# ESP32S2-new_sensor_device_v1_0-_ENV_MOT_.net
KiCad netlist of a schematic drawn in EasyEDA
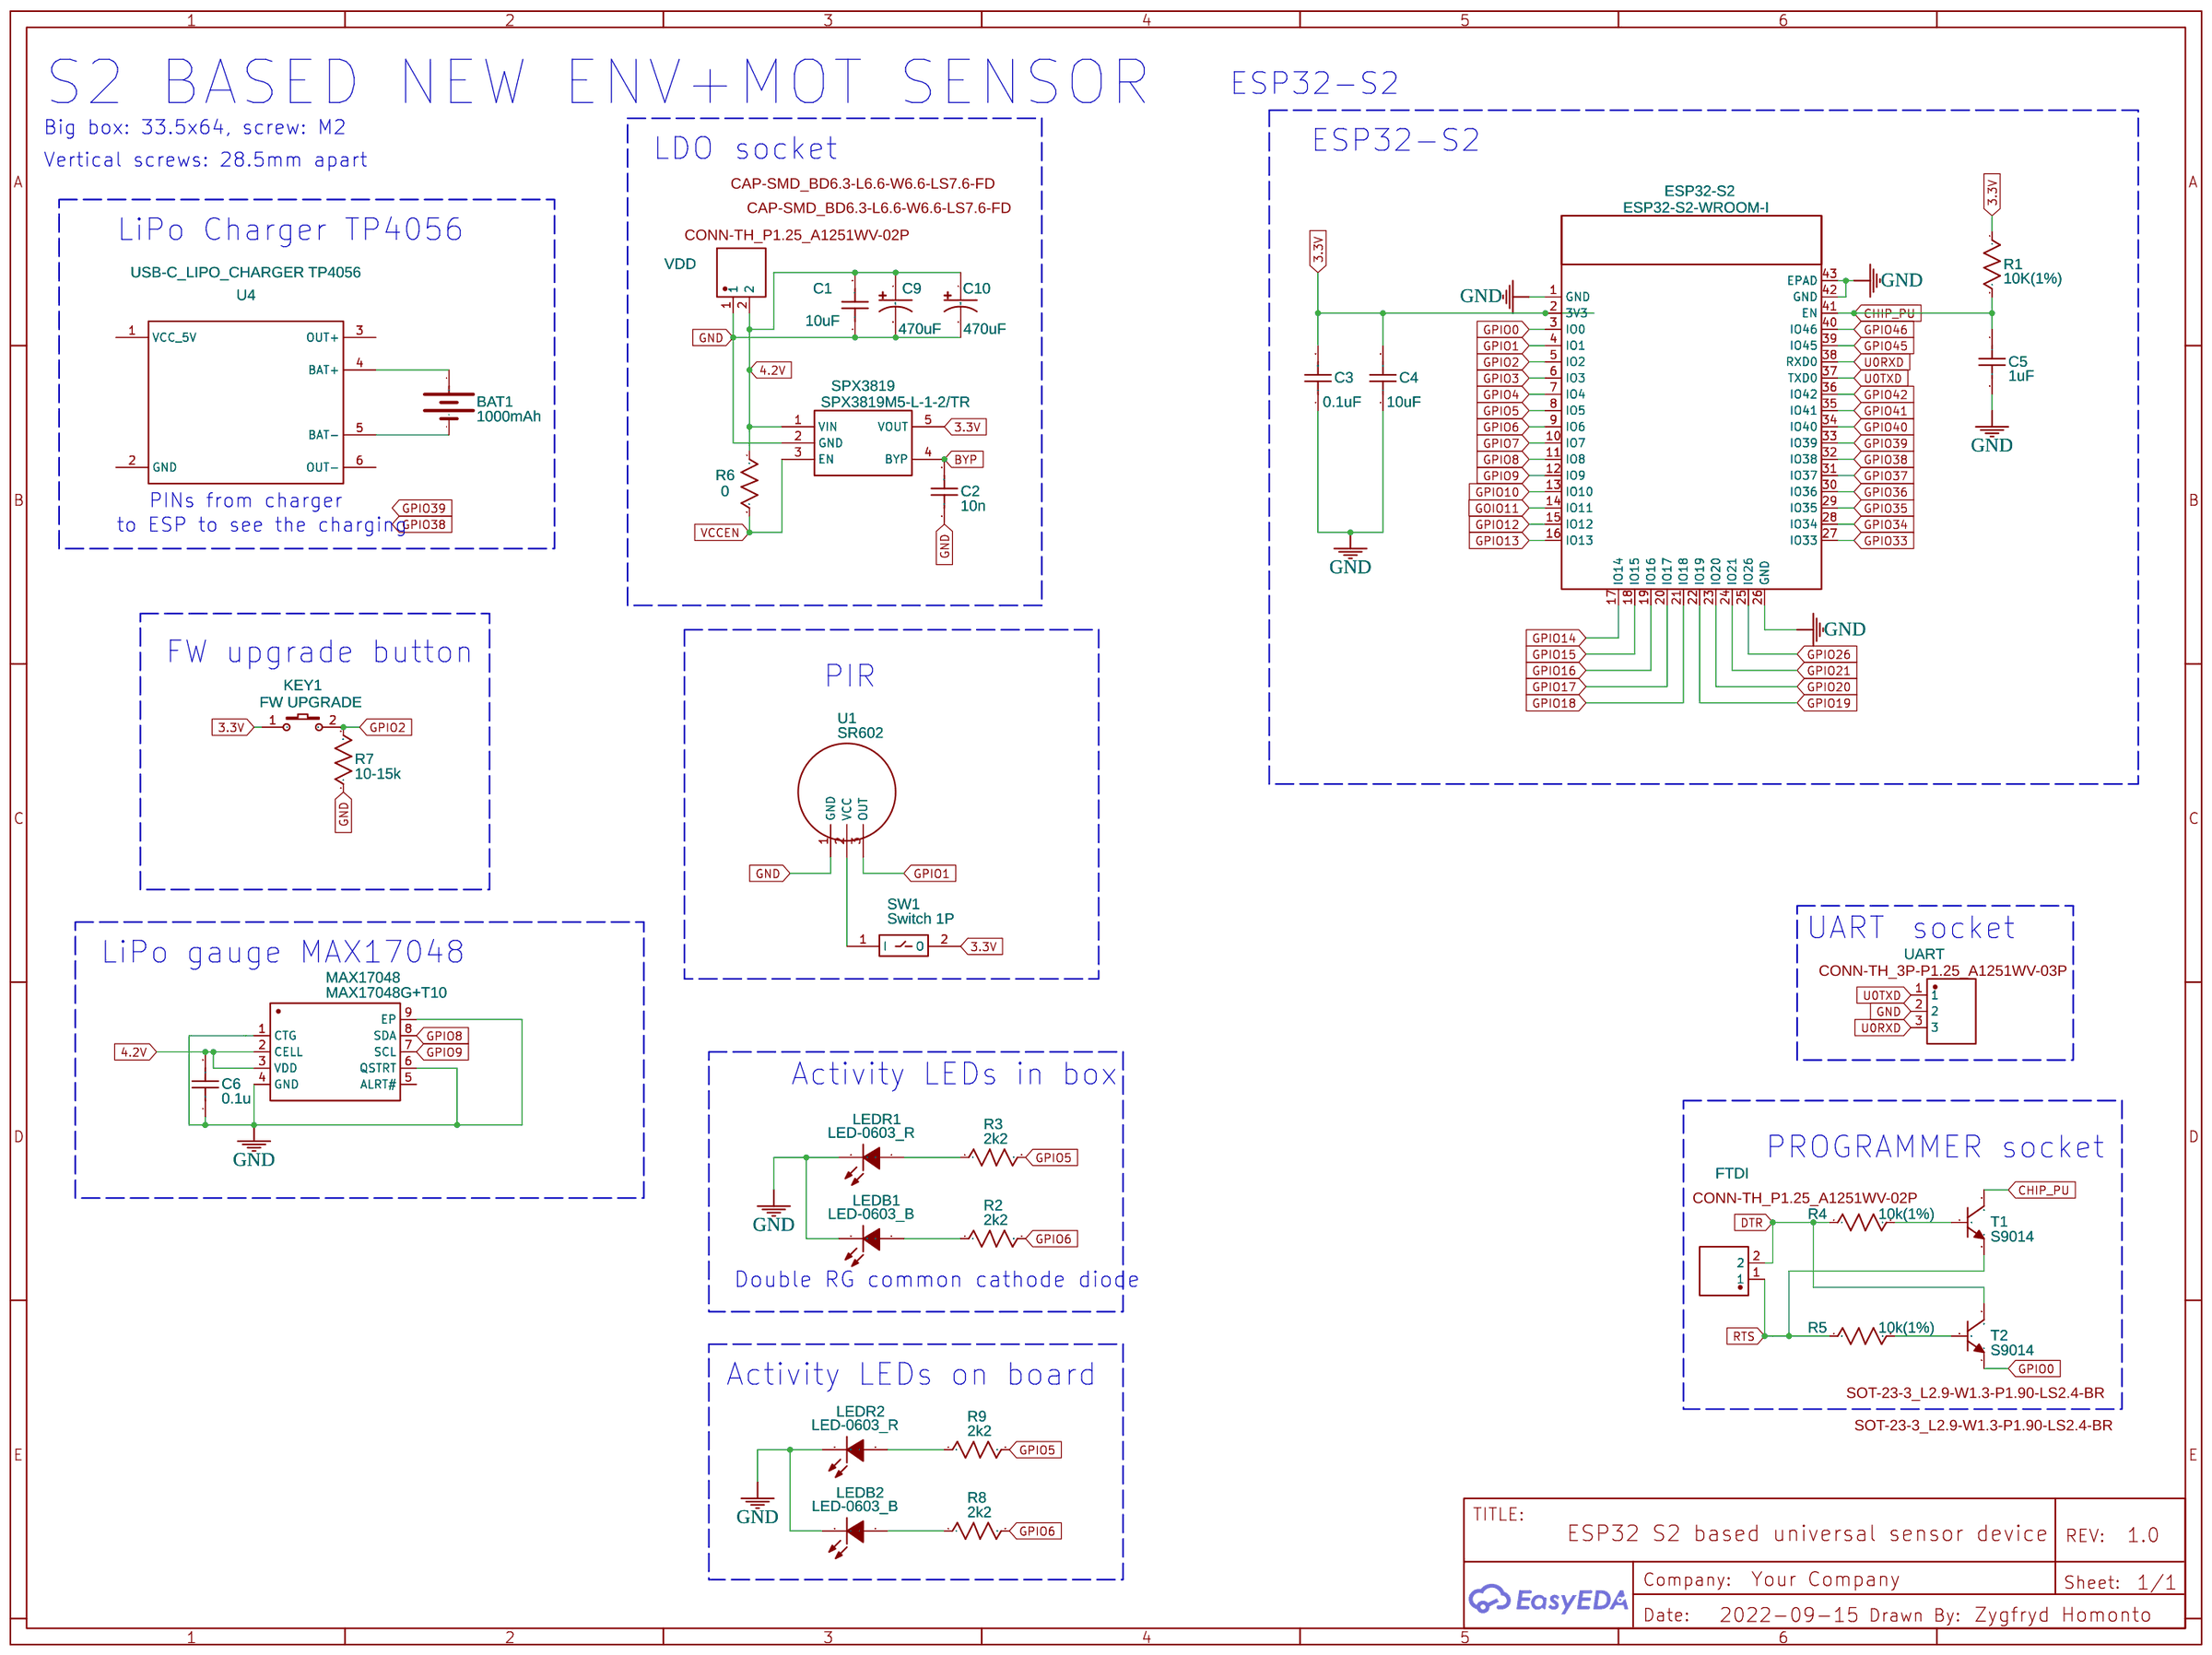
[diagram p0: schematic sheet]

(export (version "E")
  (design (tool "Eeschema 10.0.6"))
  (components
    (comp (ref "BAT1") (value "1000mAh") (libsource (lib "") (part "BATTERY")))
    (comp (ref "C1") (value "10uF") (libsource (lib "") (part "C_0201_US")))
    (comp (ref "C2") (value "10n") (libsource (lib "") (part "C_0603_US")))
    (comp (ref "C3") (value "0.1uF") (libsource (lib "") (part "C_0201_US")))
    (comp (ref "C4") (value "10uF") (libsource (lib "") (part "C_0201_US")))
    (comp (ref "C5") (value "1uF") (libsource (lib "") (part "C_0201_US_1")))
    (comp (ref "C6") (value "0.1u") (libsource (lib "") (part "C_0603_US")))
    (comp (ref "C9")
      (value "470uF")
      (fields
        (field (name "BOM_Manufacturer Part") "BXJ-16V220-6.3*7.7")
        (field (name "BOM_Supplier Part") "C165635")
      )
      (libsource (lib "") (part "BXJ-16V220-6.3*7.7_1"))
    )
    (comp (ref "C10")
      (value "470uF")
      (fields
        (field (name "BOM_Manufacturer Part") "BXJ-16V220-6.3*7.7")
        (field (name "BOM_Supplier Part") "C165635")
      )
      (libsource (lib "") (part "BXJ-16V220-6.3*7.7"))
    )
    (comp (ref "ESP32-S2")
      (value "ESP32-S2-WROOM-I")
      (fields (field (name "BOM_Manufacturer Part") "ESP32-S2-WROOM"))
      (libsource (lib "") (part "ESP32-S2-WROOM"))
    )
    (comp (ref "FTDI")
      (value "A1251WR-2P")
      (fields (field (name "BOM_Supplier Part") "C225097"))
      (libsource (lib "") (part "A1251WR-2P"))
    )
    (comp (ref "KEY1")
      (value "FW UPGRADE")
      (fields
        (field (name "BOM_Manufacturer Part") "K2-1107ST-A4SW-06")
        (field (name "BOM_Supplier Part") "C118141")
      )
      (libsource (lib "") (part "K2-3.6×6.1_SMD"))
    )
    (comp (ref "LEDB1")
      (value "LED-0603_B")
      (fields
        (field (name "BOM_Manufacturer Part") "19-217/BHC-ZL1M2RY/3T")
        (field (name "BOM_Supplier Part") "C72041")
      )
      (libsource (lib "") (part "LED-0603_B"))
    )
    (comp (ref "LEDB2")
      (value "LED-0603_B")
      (fields
        (field (name "BOM_Manufacturer Part") "19-217/BHC-ZL1M2RY/3T")
        (field (name "BOM_Supplier Part") "C72041")
      )
      (libsource (lib "") (part "LED-0603_B"))
    )
    (comp (ref "LEDR1")
      (value "LED-0603_R")
      (fields
        (field (name "BOM_Manufacturer Part") "19-217/R6C-AL1M2VY/3T")
        (field (name "BOM_Supplier Part") "C72044")
      )
      (libsource (lib "") (part "LED-0603_R"))
    )
    (comp (ref "LEDR2")
      (value "LED-0603_R")
      (fields
        (field (name "BOM_Manufacturer Part") "19-217/R6C-AL1M2VY/3T")
        (field (name "BOM_Supplier Part") "C72044")
      )
      (libsource (lib "") (part "LED-0603_R"))
    )
    (comp (ref "MAX17048")
      (value "MAX17048G+T10")
      (fields (field (name "BOM_Supplier Part") "C2682616"))
      (libsource (lib "") (part "MAX17048G+T10"))
    )
    (comp (ref "R1") (value "10K(1%)") (libsource (lib "") (part "R_0201_US_2")))
    (comp (ref "R2") (value "2k2") (libsource (lib "") (part "R_0201_US")))
    (comp (ref "R3") (value "2k2") (libsource (lib "") (part "R_0201_US")))
    (comp (ref "R4") (value "10k(1%)") (libsource (lib "") (part "R_0201_US")))
    (comp (ref "R5") (value "10k(1%)") (libsource (lib "") (part "R_0201_US")))
    (comp (ref "R6") (value "0") (libsource (lib "") (part "R_0201_US_2")))
    (comp (ref "R7") (value "10-15k") (libsource (lib "") (part "R_0201_US_1")))
    (comp (ref "R8") (value "2k2") (libsource (lib "") (part "R_0201_US")))
    (comp (ref "R9") (value "2k2") (libsource (lib "") (part "R_0201_US")))
    (comp (ref "SPX3819")
      (value "SPX3819M5-L-1-2/TR")
      (fields (field (name "BOM_Supplier Part") "C54988"))
      (libsource (lib "") (part "SPX3819M5-L-1-2/TR"))
    )
    (comp (ref "SW1") (value "Switch 1P") (libsource (lib "") (part "Switch 1P")))
    (comp (ref "T1")
      (value "S9014")
      (fields
        (field (name "BOM_Manufacturer Part") "S9014LT1 (S9014 J6)")
        (field (name "BOM_Supplier Part") "C2148")
      )
      (libsource (lib "") (part "S9014LT1 (S9014 J6)"))
    )
    (comp (ref "T2")
      (value "S9014")
      (fields
        (field (name "BOM_Manufacturer Part") "S9014LT1 (S9014 J6)")
        (field (name "BOM_Supplier Part") "C2148")
      )
      (libsource (lib "") (part "S9014LT1 (S9014 J6)_1"))
    )
    (comp (ref "U1") (value "SR602") (libsource (lib "") (part "SR602")))
    (comp (ref "U4") (value "USB-C_LIPO_CHARGER TP4056") (libsource (lib "") (part "USB_LIPO_CHARGER")))
    (comp (ref "UART")
      (value "A1251WR-3P")
      (fields (field (name "BOM_Supplier Part") "C225098"))
      (libsource (lib "") (part "A1251WR-3P"))
    )
    (comp (ref "VDD")
      (value "A1251WR-2P")
      (fields (field (name "BOM_Supplier Part") "C225097"))
      (libsource (lib "") (part "A1251WR-2P_1"))
    )
  )
  (nets
    (net (code "1") (name "3.3V") (class "Default")
      (node (ref "C3") (pin "2") (pinfunction "2_2") (pintype "unspecified"))
      (node (ref "C4") (pin "2") (pinfunction "2_2") (pintype "unspecified"))
      (node (ref "ESP32-S2") (pin "2") (pinfunction "3V3_2") (pintype "unspecified"))
      (node (ref "KEY1") (pin "1") (pinfunction "1_1") (pintype "unspecified"))
      (node (ref "R1") (pin "1") (pinfunction "1_1") (pintype "unspecified"))
      (node (ref "SPX3819") (pin "5") (pinfunction "VOUT_5") (pintype "unspecified"))
      (node (ref "SW1") (pin "2") (pinfunction "O_2") (pintype "unspecified"))
    )
    (net (code "2") (name "4.2V") (class "Default")
      (node (ref "C1") (pin "2") (pinfunction "2_2") (pintype "unspecified"))
      (node (ref "C10") (pin "1") (pinfunction "1_1") (pintype "unspecified"))
      (node (ref "C6") (pin "2") (pinfunction "2_2") (pintype "unspecified"))
      (node (ref "C9") (pin "1") (pinfunction "1_1") (pintype "unspecified"))
      (node (ref "MAX17048") (pin "2") (pinfunction "CELL_2") (pintype "unspecified"))
      (node (ref "MAX17048") (pin "3") (pinfunction "VDD_3") (pintype "unspecified"))
      (node (ref "R6") (pin "1") (pinfunction "1_1") (pintype "unspecified"))
      (node (ref "SPX3819") (pin "1") (pinfunction "VIN_1") (pintype "unspecified"))
      (node (ref "VDD") (pin "2") (pinfunction "2_2") (pintype "unspecified"))
    )
    (net (code "3") (name "BYP") (class "Default")
      (node (ref "C2") (pin "2") (pinfunction "2_2") (pintype "unspecified"))
      (node (ref "SPX3819") (pin "4") (pinfunction "BYP_4") (pintype "unspecified"))
    )
    (net (code "4") (name "CHIP_PU") (class "Default")
      (node (ref "C5") (pin "1") (pinfunction "1_1") (pintype "unspecified"))
      (node (ref "ESP32-S2") (pin "41") (pinfunction "EN_41") (pintype "unspecified"))
      (node (ref "R1") (pin "2") (pinfunction "2_2") (pintype "unspecified"))
      (node (ref "T1") (pin "3") (pinfunction "C_3") (pintype "unspecified"))
    )
    (net (code "5") (name "DTR") (class "Default")
      (node (ref "FTDI") (pin "2") (pinfunction "2_2") (pintype "unspecified"))
      (node (ref "R4") (pin "1") (pinfunction "1_1") (pintype "unspecified"))
      (node (ref "T2") (pin "3") (pinfunction "C_3") (pintype "unspecified"))
    )
    (net (code "6") (name "GND") (class "Default")
      (node (ref "C1") (pin "1") (pinfunction "1_1") (pintype "unspecified"))
      (node (ref "C10") (pin "2") (pinfunction "2_2") (pintype "unspecified"))
      (node (ref "C2") (pin "1") (pinfunction "1_1") (pintype "unspecified"))
      (node (ref "C3") (pin "1") (pinfunction "1_1") (pintype "unspecified"))
      (node (ref "C4") (pin "1") (pinfunction "1_1") (pintype "unspecified"))
      (node (ref "C5") (pin "2") (pinfunction "2_2") (pintype "unspecified"))
      (node (ref "C6") (pin "1") (pinfunction "1_1") (pintype "unspecified"))
      (node (ref "C9") (pin "2") (pinfunction "2_2") (pintype "unspecified"))
      (node (ref "ESP32-S2") (pin "1") (pinfunction "GND_1") (pintype "unspecified"))
      (node (ref "ESP32-S2") (pin "26") (pinfunction "GND_26") (pintype "unspecified"))
      (node (ref "ESP32-S2") (pin "42") (pinfunction "GND_42") (pintype "unspecified"))
      (node (ref "ESP32-S2") (pin "43") (pinfunction "EPAD_43") (pintype "unspecified"))
      (node (ref "LEDB1") (pin "2") (pinfunction "2_2") (pintype "unspecified"))
      (node (ref "LEDB2") (pin "2") (pinfunction "2_2") (pintype "unspecified"))
      (node (ref "LEDR1") (pin "2") (pinfunction "2_2") (pintype "unspecified"))
      (node (ref "LEDR2") (pin "2") (pinfunction "2_2") (pintype "unspecified"))
      (node (ref "MAX17048") (pin "1") (pinfunction "CTG_1") (pintype "unspecified"))
      (node (ref "MAX17048") (pin "4") (pinfunction "GND_4") (pintype "unspecified"))
      (node (ref "MAX17048") (pin "6") (pinfunction "QSTRT_6") (pintype "unspecified"))
      (node (ref "MAX17048") (pin "9") (pinfunction "EP_9") (pintype "unspecified"))
      (node (ref "R7") (pin "1") (pinfunction "1_1") (pintype "unspecified"))
      (node (ref "SPX3819") (pin "2") (pinfunction "GND_2") (pintype "unspecified"))
      (node (ref "U1") (pin "1") (pinfunction "GND_1") (pintype "unspecified"))
      (node (ref "UART") (pin "2") (pinfunction "2_2") (pintype "unspecified"))
      (node (ref "VDD") (pin "1") (pinfunction "1_1") (pintype "unspecified"))
    )
    (net (code "7") (name "GOIO11") (class "Default")
      (node (ref "ESP32-S2") (pin "14") (pinfunction "IO11_14") (pintype "unspecified"))
    )
    (net (code "8") (name "GPIO0") (class "Default")
      (node (ref "ESP32-S2") (pin "3") (pinfunction "IO0_3") (pintype "unspecified"))
      (node (ref "T2") (pin "2") (pinfunction "E_2") (pintype "unspecified"))
    )
    (net (code "9") (name "GPIO1") (class "Default")
      (node (ref "ESP32-S2") (pin "4") (pinfunction "IO1_4") (pintype "unspecified"))
      (node (ref "U1") (pin "3") (pinfunction "OUT_3") (pintype "unspecified"))
    )
    (net (code "10") (name "GPIO2") (class "Default")
      (node (ref "ESP32-S2") (pin "5") (pinfunction "IO2_5") (pintype "unspecified"))
      (node (ref "KEY1") (pin "2") (pinfunction "2_2") (pintype "unspecified"))
      (node (ref "R7") (pin "2") (pinfunction "2_2") (pintype "unspecified"))
    )
    (net (code "11") (name "GPIO3") (class "Default")
      (node (ref "ESP32-S2") (pin "6") (pinfunction "IO3_6") (pintype "unspecified"))
    )
    (net (code "12") (name "GPIO4") (class "Default")
      (node (ref "ESP32-S2") (pin "7") (pinfunction "IO4_7") (pintype "unspecified"))
    )
    (net (code "13") (name "GPIO5") (class "Default")
      (node (ref "ESP32-S2") (pin "8") (pinfunction "IO5_8") (pintype "unspecified"))
      (node (ref "R3") (pin "2") (pinfunction "2_2") (pintype "unspecified"))
      (node (ref "R9") (pin "2") (pinfunction "2_2") (pintype "unspecified"))
    )
    (net (code "14") (name "GPIO6") (class "Default")
      (node (ref "ESP32-S2") (pin "9") (pinfunction "IO6_9") (pintype "unspecified"))
      (node (ref "R2") (pin "2") (pinfunction "2_2") (pintype "unspecified"))
      (node (ref "R8") (pin "2") (pinfunction "2_2") (pintype "unspecified"))
    )
    (net (code "15") (name "GPIO7") (class "Default")
      (node (ref "ESP32-S2") (pin "10") (pinfunction "IO7_10") (pintype "unspecified"))
    )
    (net (code "16") (name "GPIO8") (class "Default")
      (node (ref "ESP32-S2") (pin "11") (pinfunction "IO8_11") (pintype "unspecified"))
      (node (ref "MAX17048") (pin "8") (pinfunction "SDA_8") (pintype "unspecified"))
    )
    (net (code "17") (name "GPIO9") (class "Default")
      (node (ref "ESP32-S2") (pin "12") (pinfunction "IO9_12") (pintype "unspecified"))
      (node (ref "MAX17048") (pin "7") (pinfunction "SCL_7") (pintype "unspecified"))
    )
    (net (code "18") (name "GPIO10") (class "Default")
      (node (ref "ESP32-S2") (pin "13") (pinfunction "IO10_13") (pintype "unspecified"))
    )
    (net (code "19") (name "GPIO12") (class "Default")
      (node (ref "ESP32-S2") (pin "15") (pinfunction "IO12_15") (pintype "unspecified"))
    )
    (net (code "20") (name "GPIO13") (class "Default")
      (node (ref "ESP32-S2") (pin "16") (pinfunction "IO13_16") (pintype "unspecified"))
    )
    (net (code "21") (name "GPIO14") (class "Default")
      (node (ref "ESP32-S2") (pin "17") (pinfunction "IO14_17") (pintype "unspecified"))
    )
    (net (code "22") (name "GPIO15") (class "Default")
      (node (ref "ESP32-S2") (pin "18") (pinfunction "IO15_18") (pintype "unspecified"))
    )
    (net (code "23") (name "GPIO16") (class "Default")
      (node (ref "ESP32-S2") (pin "19") (pinfunction "IO16_19") (pintype "unspecified"))
    )
    (net (code "24") (name "GPIO17") (class "Default")
      (node (ref "ESP32-S2") (pin "20") (pinfunction "IO17_20") (pintype "unspecified"))
    )
    (net (code "25") (name "GPIO18") (class "Default")
      (node (ref "ESP32-S2") (pin "21") (pinfunction "IO18_21") (pintype "unspecified"))
    )
    (net (code "26") (name "GPIO19") (class "Default")
      (node (ref "ESP32-S2") (pin "22") (pinfunction "IO19_22") (pintype "unspecified"))
    )
    (net (code "27") (name "GPIO20") (class "Default")
      (node (ref "ESP32-S2") (pin "23") (pinfunction "IO20_23") (pintype "unspecified"))
    )
    (net (code "28") (name "GPIO21") (class "Default")
      (node (ref "ESP32-S2") (pin "24") (pinfunction "IO21_24") (pintype "unspecified"))
    )
    (net (code "29") (name "GPIO26") (class "Default")
      (node (ref "ESP32-S2") (pin "25") (pinfunction "IO26_25") (pintype "unspecified"))
    )
    (net (code "30") (name "GPIO33") (class "Default")
      (node (ref "ESP32-S2") (pin "27") (pinfunction "IO33_27") (pintype "unspecified"))
    )
    (net (code "31") (name "GPIO34") (class "Default")
      (node (ref "ESP32-S2") (pin "28") (pinfunction "IO34_28") (pintype "unspecified"))
    )
    (net (code "32") (name "GPIO35") (class "Default")
      (node (ref "ESP32-S2") (pin "29") (pinfunction "IO35_29") (pintype "unspecified"))
    )
    (net (code "33") (name "GPIO36") (class "Default")
      (node (ref "ESP32-S2") (pin "30") (pinfunction "IO36_30") (pintype "unspecified"))
    )
    (net (code "34") (name "GPIO37") (class "Default")
      (node (ref "ESP32-S2") (pin "31") (pinfunction "IO37_31") (pintype "unspecified"))
    )
    (net (code "35") (name "GPIO38") (class "Default")
      (node (ref "ESP32-S2") (pin "32") (pinfunction "IO38_32") (pintype "unspecified"))
    )
    (net (code "36") (name "GPIO39") (class "Default")
      (node (ref "ESP32-S2") (pin "33") (pinfunction "IO39_33") (pintype "unspecified"))
    )
    (net (code "37") (name "GPIO40") (class "Default")
      (node (ref "ESP32-S2") (pin "34") (pinfunction "IO40_34") (pintype "unspecified"))
    )
    (net (code "38") (name "GPIO41") (class "Default")
      (node (ref "ESP32-S2") (pin "35") (pinfunction "IO41_35") (pintype "unspecified"))
    )
    (net (code "39") (name "GPIO42") (class "Default")
      (node (ref "ESP32-S2") (pin "36") (pinfunction "IO42_36") (pintype "unspecified"))
    )
    (net (code "40") (name "GPIO45") (class "Default")
      (node (ref "ESP32-S2") (pin "39") (pinfunction "IO45_39") (pintype "unspecified"))
    )
    (net (code "41") (name "GPIO46") (class "Default")
      (node (ref "ESP32-S2") (pin "40") (pinfunction "IO46_40") (pintype "unspecified"))
    )
    (net (code "42") (name "Net-(LEDB1-Pad1)") (class "Default")
      (node (ref "LEDB1") (pin "1") (pinfunction "1_1") (pintype "unspecified"))
      (node (ref "R2") (pin "1") (pinfunction "1_1") (pintype "unspecified"))
    )
    (net (code "43") (name "Net-(LEDB2-Pad1)") (class "Default")
      (node (ref "LEDB2") (pin "1") (pinfunction "1_1") (pintype "unspecified"))
      (node (ref "R8") (pin "1") (pinfunction "1_1") (pintype "unspecified"))
    )
    (net (code "44") (name "Net-(LEDR1-Pad1)") (class "Default")
      (node (ref "LEDR1") (pin "1") (pinfunction "1_1") (pintype "unspecified"))
      (node (ref "R3") (pin "1") (pinfunction "1_1") (pintype "unspecified"))
    )
    (net (code "45") (name "Net-(LEDR2-Pad1)") (class "Default")
      (node (ref "LEDR2") (pin "1") (pinfunction "1_1") (pintype "unspecified"))
      (node (ref "R9") (pin "1") (pinfunction "1_1") (pintype "unspecified"))
    )
    (net (code "46") (name "Net-(SW1-I)") (class "Default")
      (node (ref "SW1") (pin "1") (pinfunction "I_1") (pintype "unspecified"))
      (node (ref "U1") (pin "2") (pinfunction "VCC_2") (pintype "unspecified"))
    )
    (net (code "47") (name "Net-(T1-B)") (class "Default")
      (node (ref "R4") (pin "2") (pinfunction "2_2") (pintype "unspecified"))
      (node (ref "T1") (pin "1") (pinfunction "B_1") (pintype "unspecified"))
    )
    (net (code "48") (name "Net-(T2-B)") (class "Default")
      (node (ref "R5") (pin "2") (pinfunction "2_2") (pintype "unspecified"))
      (node (ref "T2") (pin "1") (pinfunction "B_1") (pintype "unspecified"))
    )
    (net (code "49") (name "Net-(U4-BAT+)") (class "Default")
      (node (ref "BAT1") (pin "+") (pinfunction "+_+") (pintype "passive"))
      (node (ref "U4") (pin "4") (pinfunction "BAT+_4") (pintype "unspecified"))
    )
    (net (code "50") (name "Net-(U4-BAT-)") (class "Default")
      (node (ref "BAT1") (pin "-") (pinfunction "-_-") (pintype "passive"))
      (node (ref "U4") (pin "5") (pinfunction "BAT-_5") (pintype "unspecified"))
    )
    (net (code "51") (name "RTS") (class "Default")
      (node (ref "FTDI") (pin "1") (pinfunction "1_1") (pintype "unspecified"))
      (node (ref "R5") (pin "1") (pinfunction "1_1") (pintype "unspecified"))
      (node (ref "T1") (pin "2") (pinfunction "E_2") (pintype "unspecified"))
    )
    (net (code "52") (name "U0RXD") (class "Default")
      (node (ref "ESP32-S2") (pin "38") (pinfunction "RXD0_38") (pintype "unspecified"))
      (node (ref "UART") (pin "3") (pinfunction "3_3") (pintype "unspecified"))
    )
    (net (code "53") (name "U0TXD") (class "Default")
      (node (ref "ESP32-S2") (pin "37") (pinfunction "TXD0_37") (pintype "unspecified"))
      (node (ref "UART") (pin "1") (pinfunction "1_1") (pintype "unspecified"))
    )
    (net (code "54") (name "VCCEN") (class "Default")
      (node (ref "R6") (pin "2") (pinfunction "2_2") (pintype "unspecified"))
      (node (ref "SPX3819") (pin "3") (pinfunction "EN_3") (pintype "unspecified"))
    )
    (net (code "55") (name "unconnected-(MAX17048-ALRT#-Pad5)") (class "Default")
      (node (ref "MAX17048") (pin "5") (pinfunction "ALRT#_5") (pintype "unspecified"))
    )
    (net (code "56") (name "unconnected-(U4-GND-Pad2)") (class "Default")
      (node (ref "U4") (pin "2") (pinfunction "GND_2") (pintype "unspecified"))
    )
    (net (code "57") (name "unconnected-(U4-OUT+-Pad3)") (class "Default")
      (node (ref "U4") (pin "3") (pinfunction "OUT+_3") (pintype "unspecified"))
    )
    (net (code "58") (name "unconnected-(U4-OUT--Pad6)") (class "Default")
      (node (ref "U4") (pin "6") (pinfunction "OUT-_6") (pintype "unspecified"))
    )
    (net (code "59") (name "unconnected-(U4-VCC_5V-Pad1)") (class "Default")
      (node (ref "U4") (pin "1") (pinfunction "VCC_5V_1") (pintype "unspecified"))
    )
  )
)
